# ERAM100.net
KiCad netlist of a schematic drawn in EAGLE
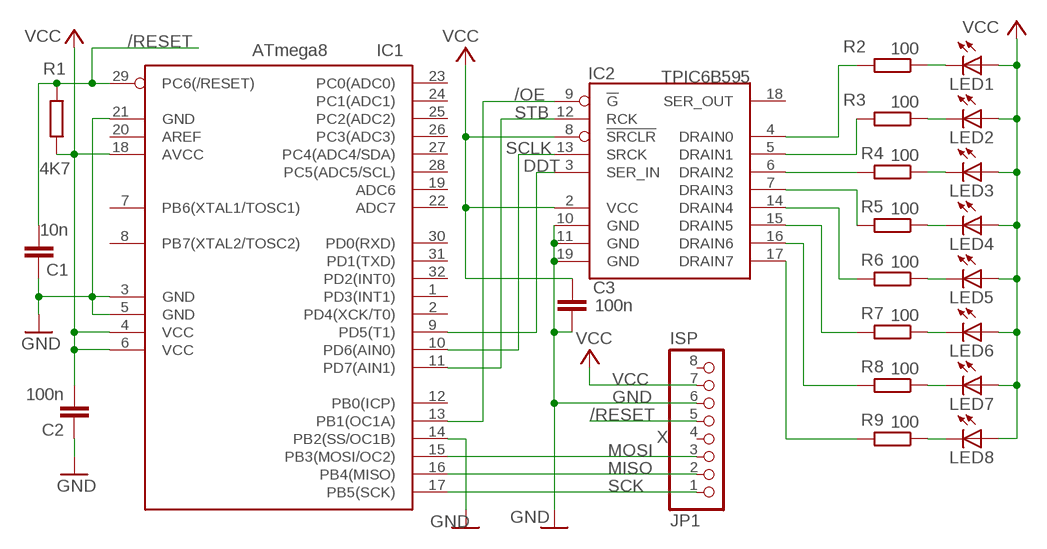
[diagram p0: schematic, sheet 1]

(export (version "E")
  (design (tool "Eeschema 10.0.6"))
  (components
    (comp (ref "C1")
      (value "10n")
      (footprint "eagle-import:C0805")
      (libsource (lib "eagle-import") (part "C-EUC0805"))
    )
    (comp (ref "C2")
      (value "100n")
      (footprint "eagle-import:C0805")
      (libsource (lib "eagle-import") (part "C-EUC0805"))
    )
    (comp (ref "C3")
      (value "100n")
      (footprint "eagle-import:C0805")
      (libsource (lib "eagle-import") (part "C-EUC0805"))
    )
    (comp (ref "IC1")
      (value "ATmega8")
      (footprint "eagle-import:TQFP32-08")
      (fields (field (name "MPN") "ATMEGA8-16AU"))
      (libsource (lib "eagle-import") (part "MEGA8-AI"))
    )
    (comp (ref "IC2")
      (value "TPIC6B595")
      (footprint "eagle-import:SO20W")
      (libsource (lib "eagle-import") (part "TPIC6B595DW"))
    )
    (comp (ref "JP1")
      (value "ISP")
      (footprint "eagle-import:1X08-BIG")
      (libsource (lib "eagle-import") (part "PINHD-1X8BIG"))
    )
    (comp (ref "LED1")
      (value "LED3MM")
      (footprint "eagle-import:LED3MM")
      (libsource (lib "eagle-import") (part "LED3MM"))
    )
    (comp (ref "LED2")
      (value "LED3MM")
      (footprint "eagle-import:LED3MM")
      (libsource (lib "eagle-import") (part "LED3MM"))
    )
    (comp (ref "LED3")
      (value "LED3MM")
      (footprint "eagle-import:LED3MM")
      (libsource (lib "eagle-import") (part "LED3MM"))
    )
    (comp (ref "LED4")
      (value "LED3MM")
      (footprint "eagle-import:LED3MM")
      (libsource (lib "eagle-import") (part "LED3MM"))
    )
    (comp (ref "LED5")
      (value "LED3MM")
      (footprint "eagle-import:LED3MM")
      (libsource (lib "eagle-import") (part "LED3MM"))
    )
    (comp (ref "LED6")
      (value "LED3MM")
      (footprint "eagle-import:LED3MM")
      (libsource (lib "eagle-import") (part "LED3MM"))
    )
    (comp (ref "LED7")
      (value "LED3MM")
      (footprint "eagle-import:LED3MM")
      (libsource (lib "eagle-import") (part "LED3MM"))
    )
    (comp (ref "LED8")
      (value "LED3MM")
      (footprint "eagle-import:LED3MM")
      (libsource (lib "eagle-import") (part "LED3MM"))
    )
    (comp (ref "R1")
      (value "4K7")
      (footprint "eagle-import:R0805")
      (libsource (lib "eagle-import") (part "R-EU_R0805"))
    )
    (comp (ref "R2")
      (value "100")
      (footprint "eagle-import:R0805")
      (libsource (lib "eagle-import") (part "R-EU_R0805"))
    )
    (comp (ref "R3")
      (value "100")
      (footprint "eagle-import:R0805")
      (libsource (lib "eagle-import") (part "R-EU_R0805"))
    )
    (comp (ref "R4")
      (value "100")
      (footprint "eagle-import:R0805")
      (libsource (lib "eagle-import") (part "R-EU_R0805"))
    )
    (comp (ref "R5")
      (value "100")
      (footprint "eagle-import:R0805")
      (libsource (lib "eagle-import") (part "R-EU_R0805"))
    )
    (comp (ref "R6")
      (value "100")
      (footprint "eagle-import:R0805")
      (libsource (lib "eagle-import") (part "R-EU_R0805"))
    )
    (comp (ref "R7")
      (value "100")
      (footprint "eagle-import:R0805")
      (libsource (lib "eagle-import") (part "R-EU_R0805"))
    )
    (comp (ref "R8")
      (value "100")
      (footprint "eagle-import:R0805")
      (libsource (lib "eagle-import") (part "R-EU_R0805"))
    )
    (comp (ref "R9")
      (value "100")
      (footprint "eagle-import:R0805")
      (libsource (lib "eagle-import") (part "R-EU_R0805"))
    )
  )
  (nets
    (net (code "1") (name "/DDT") (class "Default")
      (node (ref "IC1") (pin "9") (pinfunction "PD5(T1)_9") (pintype "bidirectional"))
      (node (ref "IC2") (pin "3") (pinfunction "SER_IN_3") (pintype "input"))
    )
    (net (code "2") (name "/MISO") (class "Default")
      (node (ref "IC1") (pin "16") (pinfunction "PB4(MISO)_16") (pintype "bidirectional"))
      (node (ref "JP1") (pin "2") (pinfunction "2_2") (pintype "passive"))
    )
    (net (code "3") (name "/MOSI") (class "Default")
      (node (ref "IC1") (pin "15") (pinfunction "PB3(MOSI/OC2)_15") (pintype "bidirectional"))
      (node (ref "JP1") (pin "3") (pinfunction "3_3") (pintype "passive"))
    )
    (net (code "4") (name "/SCK") (class "Default")
      (node (ref "IC1") (pin "17") (pinfunction "PB5(SCK)_17") (pintype "bidirectional"))
      (node (ref "JP1") (pin "1") (pinfunction "1_1") (pintype "passive"))
    )
    (net (code "5") (name "/SCLK") (class "Default")
      (node (ref "IC1") (pin "10") (pinfunction "PD6(AIN0)_10") (pintype "bidirectional"))
      (node (ref "IC2") (pin "13") (pinfunction "SRCK_13") (pintype "input"))
    )
    (net (code "6") (name "/STB") (class "Default")
      (node (ref "IC1") (pin "11") (pinfunction "PD7(AIN1)_11") (pintype "bidirectional"))
      (node (ref "IC2") (pin "12") (pinfunction "RCK_12") (pintype "input"))
    )
    (net (code "7") (name "/{slash}OE") (class "Default")
      (node (ref "IC1") (pin "13") (pinfunction "PB1(OC1A)_13") (pintype "bidirectional"))
      (node (ref "IC2") (pin "9") (pinfunction "~{G}_9") (pintype "input"))
    )
    (net (code "8") (name "/{slash}RESET") (class "Default")
      (node (ref "C1") (pin "2") (pinfunction "2_2") (pintype "passive"))
      (node (ref "IC1") (pin "29") (pinfunction "PC6(/RESET)_29") (pintype "bidirectional"))
      (node (ref "JP1") (pin "5") (pinfunction "5_5") (pintype "passive"))
      (node (ref "R1") (pin "2") (pinfunction "2_2") (pintype "passive"))
    )
    (net (code "9") (name "GND") (class "Default")
      (node (ref "C1") (pin "1") (pinfunction "1_1") (pintype "passive"))
      (node (ref "C2") (pin "1") (pinfunction "1_1") (pintype "passive"))
      (node (ref "C3") (pin "1") (pinfunction "1_1") (pintype "passive"))
      (node (ref "IC1") (pin "14") (pinfunction "PB2(SS/OC1B)_14") (pintype "bidirectional"))
      (node (ref "IC1") (pin "21") (pinfunction "GND_21") (pintype "power_in"))
      (node (ref "IC1") (pin "3") (pinfunction "GND_3") (pintype "power_in"))
      (node (ref "IC1") (pin "5") (pinfunction "GND_5") (pintype "power_in"))
      (node (ref "IC2") (pin "10") (pinfunction "GND_10") (pintype "power_in"))
      (node (ref "IC2") (pin "11") (pinfunction "GND_11") (pintype "power_in"))
      (node (ref "IC2") (pin "19") (pinfunction "GND_19") (pintype "power_in"))
      (node (ref "JP1") (pin "6") (pinfunction "6_6") (pintype "passive"))
    )
    (net (code "10") (name "Net-(IC2-DRAIN0)") (class "Default")
      (node (ref "IC2") (pin "4") (pinfunction "DRAIN0_4") (pintype "open_collector"))
      (node (ref "R2") (pin "2") (pinfunction "2_2") (pintype "passive"))
    )
    (net (code "11") (name "Net-(IC2-DRAIN1)") (class "Default")
      (node (ref "IC2") (pin "5") (pinfunction "DRAIN1_5") (pintype "open_collector"))
      (node (ref "R3") (pin "2") (pinfunction "2_2") (pintype "passive"))
    )
    (net (code "12") (name "Net-(IC2-DRAIN2)") (class "Default")
      (node (ref "IC2") (pin "6") (pinfunction "DRAIN2_6") (pintype "open_collector"))
      (node (ref "R4") (pin "2") (pinfunction "2_2") (pintype "passive"))
    )
    (net (code "13") (name "Net-(IC2-DRAIN3)") (class "Default")
      (node (ref "IC2") (pin "7") (pinfunction "DRAIN3_7") (pintype "open_collector"))
      (node (ref "R5") (pin "2") (pinfunction "2_2") (pintype "passive"))
    )
    (net (code "14") (name "Net-(IC2-DRAIN4)") (class "Default")
      (node (ref "IC2") (pin "14") (pinfunction "DRAIN4_14") (pintype "open_collector"))
      (node (ref "R6") (pin "2") (pinfunction "2_2") (pintype "passive"))
    )
    (net (code "15") (name "Net-(IC2-DRAIN5)") (class "Default")
      (node (ref "IC2") (pin "15") (pinfunction "DRAIN5_15") (pintype "open_collector"))
      (node (ref "R7") (pin "2") (pinfunction "2_2") (pintype "passive"))
    )
    (net (code "16") (name "Net-(IC2-DRAIN6)") (class "Default")
      (node (ref "IC2") (pin "16") (pinfunction "DRAIN6_16") (pintype "open_collector"))
      (node (ref "R8") (pin "2") (pinfunction "2_2") (pintype "passive"))
    )
    (net (code "17") (name "Net-(IC2-DRAIN7)") (class "Default")
      (node (ref "IC2") (pin "17") (pinfunction "DRAIN7_17") (pintype "open_collector"))
      (node (ref "R9") (pin "2") (pinfunction "2_2") (pintype "passive"))
    )
    (net (code "18") (name "Net-(LED1-C)") (class "Default")
      (node (ref "LED1") (pin "K") (pinfunction "C_K") (pintype "passive"))
      (node (ref "R2") (pin "1") (pinfunction "1_1") (pintype "passive"))
    )
    (net (code "19") (name "Net-(LED2-C)") (class "Default")
      (node (ref "LED2") (pin "K") (pinfunction "C_K") (pintype "passive"))
      (node (ref "R3") (pin "1") (pinfunction "1_1") (pintype "passive"))
    )
    (net (code "20") (name "Net-(LED3-C)") (class "Default")
      (node (ref "LED3") (pin "K") (pinfunction "C_K") (pintype "passive"))
      (node (ref "R4") (pin "1") (pinfunction "1_1") (pintype "passive"))
    )
    (net (code "21") (name "Net-(LED4-C)") (class "Default")
      (node (ref "LED4") (pin "K") (pinfunction "C_K") (pintype "passive"))
      (node (ref "R5") (pin "1") (pinfunction "1_1") (pintype "passive"))
    )
    (net (code "22") (name "Net-(LED5-C)") (class "Default")
      (node (ref "LED5") (pin "K") (pinfunction "C_K") (pintype "passive"))
      (node (ref "R6") (pin "1") (pinfunction "1_1") (pintype "passive"))
    )
    (net (code "23") (name "Net-(LED6-C)") (class "Default")
      (node (ref "LED6") (pin "K") (pinfunction "C_K") (pintype "passive"))
      (node (ref "R7") (pin "1") (pinfunction "1_1") (pintype "passive"))
    )
    (net (code "24") (name "Net-(LED7-C)") (class "Default")
      (node (ref "LED7") (pin "K") (pinfunction "C_K") (pintype "passive"))
      (node (ref "R8") (pin "1") (pinfunction "1_1") (pintype "passive"))
    )
    (net (code "25") (name "Net-(LED8-C)") (class "Default")
      (node (ref "LED8") (pin "K") (pinfunction "C_K") (pintype "passive"))
      (node (ref "R9") (pin "1") (pinfunction "1_1") (pintype "passive"))
    )
    (net (code "26") (name "VCC") (class "Default")
      (node (ref "C2") (pin "2") (pinfunction "2_2") (pintype "passive"))
      (node (ref "C3") (pin "2") (pinfunction "2_2") (pintype "passive"))
      (node (ref "IC1") (pin "18") (pinfunction "AVCC_18") (pintype "power_in"))
      (node (ref "IC1") (pin "4") (pinfunction "VCC_4") (pintype "power_in"))
      (node (ref "IC1") (pin "6") (pinfunction "VCC_6") (pintype "power_in"))
      (node (ref "IC2") (pin "2") (pinfunction "VCC_2") (pintype "power_in"))
      (node (ref "IC2") (pin "8") (pinfunction "~{SRCLR}_8") (pintype "input"))
      (node (ref "JP1") (pin "7") (pinfunction "7_7") (pintype "passive"))
      (node (ref "LED1") (pin "A") (pinfunction "A_A") (pintype "passive"))
      (node (ref "LED2") (pin "A") (pinfunction "A_A") (pintype "passive"))
      (node (ref "LED3") (pin "A") (pinfunction "A_A") (pintype "passive"))
      (node (ref "LED4") (pin "A") (pinfunction "A_A") (pintype "passive"))
      (node (ref "LED5") (pin "A") (pinfunction "A_A") (pintype "passive"))
      (node (ref "LED6") (pin "A") (pinfunction "A_A") (pintype "passive"))
      (node (ref "LED7") (pin "A") (pinfunction "A_A") (pintype "passive"))
      (node (ref "LED8") (pin "A") (pinfunction "A_A") (pintype "passive"))
      (node (ref "R1") (pin "1") (pinfunction "1_1") (pintype "passive"))
    )
    (net (code "27") (name "unconnected-(IC1-ADC6-Pad19)") (class "Default")
      (node (ref "IC1") (pin "19") (pinfunction "ADC6_19") (pintype "bidirectional"))
    )
    (net (code "28") (name "unconnected-(IC1-ADC7-Pad22)") (class "Default")
      (node (ref "IC1") (pin "22") (pinfunction "ADC7_22") (pintype "bidirectional"))
    )
    (net (code "29") (name "unconnected-(IC1-AREF-Pad20)") (class "Default")
      (node (ref "IC1") (pin "20") (pinfunction "AREF_20") (pintype "passive"))
    )
    (net (code "30") (name "unconnected-(IC1-PB0(ICP)-Pad12)") (class "Default")
      (node (ref "IC1") (pin "12") (pinfunction "PB0(ICP)_12") (pintype "bidirectional"))
    )
    (net (code "31") (name "unconnected-(IC1-PB6(XTAL1{slash}TOSC1)-Pad7)") (class "Default")
      (node (ref "IC1") (pin "7") (pinfunction "PB6(XTAL1/TOSC1)_7") (pintype "bidirectional"))
    )
    (net (code "32") (name "unconnected-(IC1-PB7(XTAL2{slash}TOSC2)-Pad8)") (class "Default")
      (node (ref "IC1") (pin "8") (pinfunction "PB7(XTAL2/TOSC2)_8") (pintype "bidirectional"))
    )
    (net (code "33") (name "unconnected-(IC1-PC0(ADC0)-Pad23)") (class "Default")
      (node (ref "IC1") (pin "23") (pinfunction "PC0(ADC0)_23") (pintype "bidirectional"))
    )
    (net (code "34") (name "unconnected-(IC1-PC1(ADC1)-Pad24)") (class "Default")
      (node (ref "IC1") (pin "24") (pinfunction "PC1(ADC1)_24") (pintype "bidirectional"))
    )
    (net (code "35") (name "unconnected-(IC1-PC2(ADC2)-Pad25)") (class "Default")
      (node (ref "IC1") (pin "25") (pinfunction "PC2(ADC2)_25") (pintype "bidirectional"))
    )
    (net (code "36") (name "unconnected-(IC1-PC3(ADC3)-Pad26)") (class "Default")
      (node (ref "IC1") (pin "26") (pinfunction "PC3(ADC3)_26") (pintype "bidirectional"))
    )
    (net (code "37") (name "unconnected-(IC1-PC4(ADC4{slash}SDA)-Pad27)") (class "Default")
      (node (ref "IC1") (pin "27") (pinfunction "PC4(ADC4/SDA)_27") (pintype "bidirectional"))
    )
    (net (code "38") (name "unconnected-(IC1-PC5(ADC5{slash}SCL)-Pad28)") (class "Default")
      (node (ref "IC1") (pin "28") (pinfunction "PC5(ADC5/SCL)_28") (pintype "bidirectional"))
    )
    (net (code "39") (name "unconnected-(IC1-PD0(RXD)-Pad30)") (class "Default")
      (node (ref "IC1") (pin "30") (pinfunction "PD0(RXD)_30") (pintype "bidirectional"))
    )
    (net (code "40") (name "unconnected-(IC1-PD1(TXD)-Pad31)") (class "Default")
      (node (ref "IC1") (pin "31") (pinfunction "PD1(TXD)_31") (pintype "bidirectional"))
    )
    (net (code "41") (name "unconnected-(IC1-PD2(INT0)-Pad32)") (class "Default")
      (node (ref "IC1") (pin "32") (pinfunction "PD2(INT0)_32") (pintype "bidirectional"))
    )
    (net (code "42") (name "unconnected-(IC1-PD3(INT1)-Pad1)") (class "Default")
      (node (ref "IC1") (pin "1") (pinfunction "PD3(INT1)_1") (pintype "bidirectional"))
    )
    (net (code "43") (name "unconnected-(IC1-PD4(XCK{slash}T0)-Pad2)") (class "Default")
      (node (ref "IC1") (pin "2") (pinfunction "PD4(XCK/T0)_2") (pintype "bidirectional"))
    )
    (net (code "44") (name "unconnected-(IC2-SER_OUT-Pad18)") (class "Default")
      (node (ref "IC2") (pin "18") (pinfunction "SER_OUT_18") (pintype "output"))
    )
    (net (code "45") (name "unconnected-(JP1-Pad4)") (class "Default")
      (node (ref "JP1") (pin "4") (pinfunction "4_4") (pintype "passive"))
    )
    (net (code "46") (name "unconnected-(JP1-Pad8)") (class "Default")
      (node (ref "JP1") (pin "8") (pinfunction "8_8") (pintype "passive"))
    )
  )
)
